# Single_Board.net
KiCad netlist of a schematic drawn in EAGLE
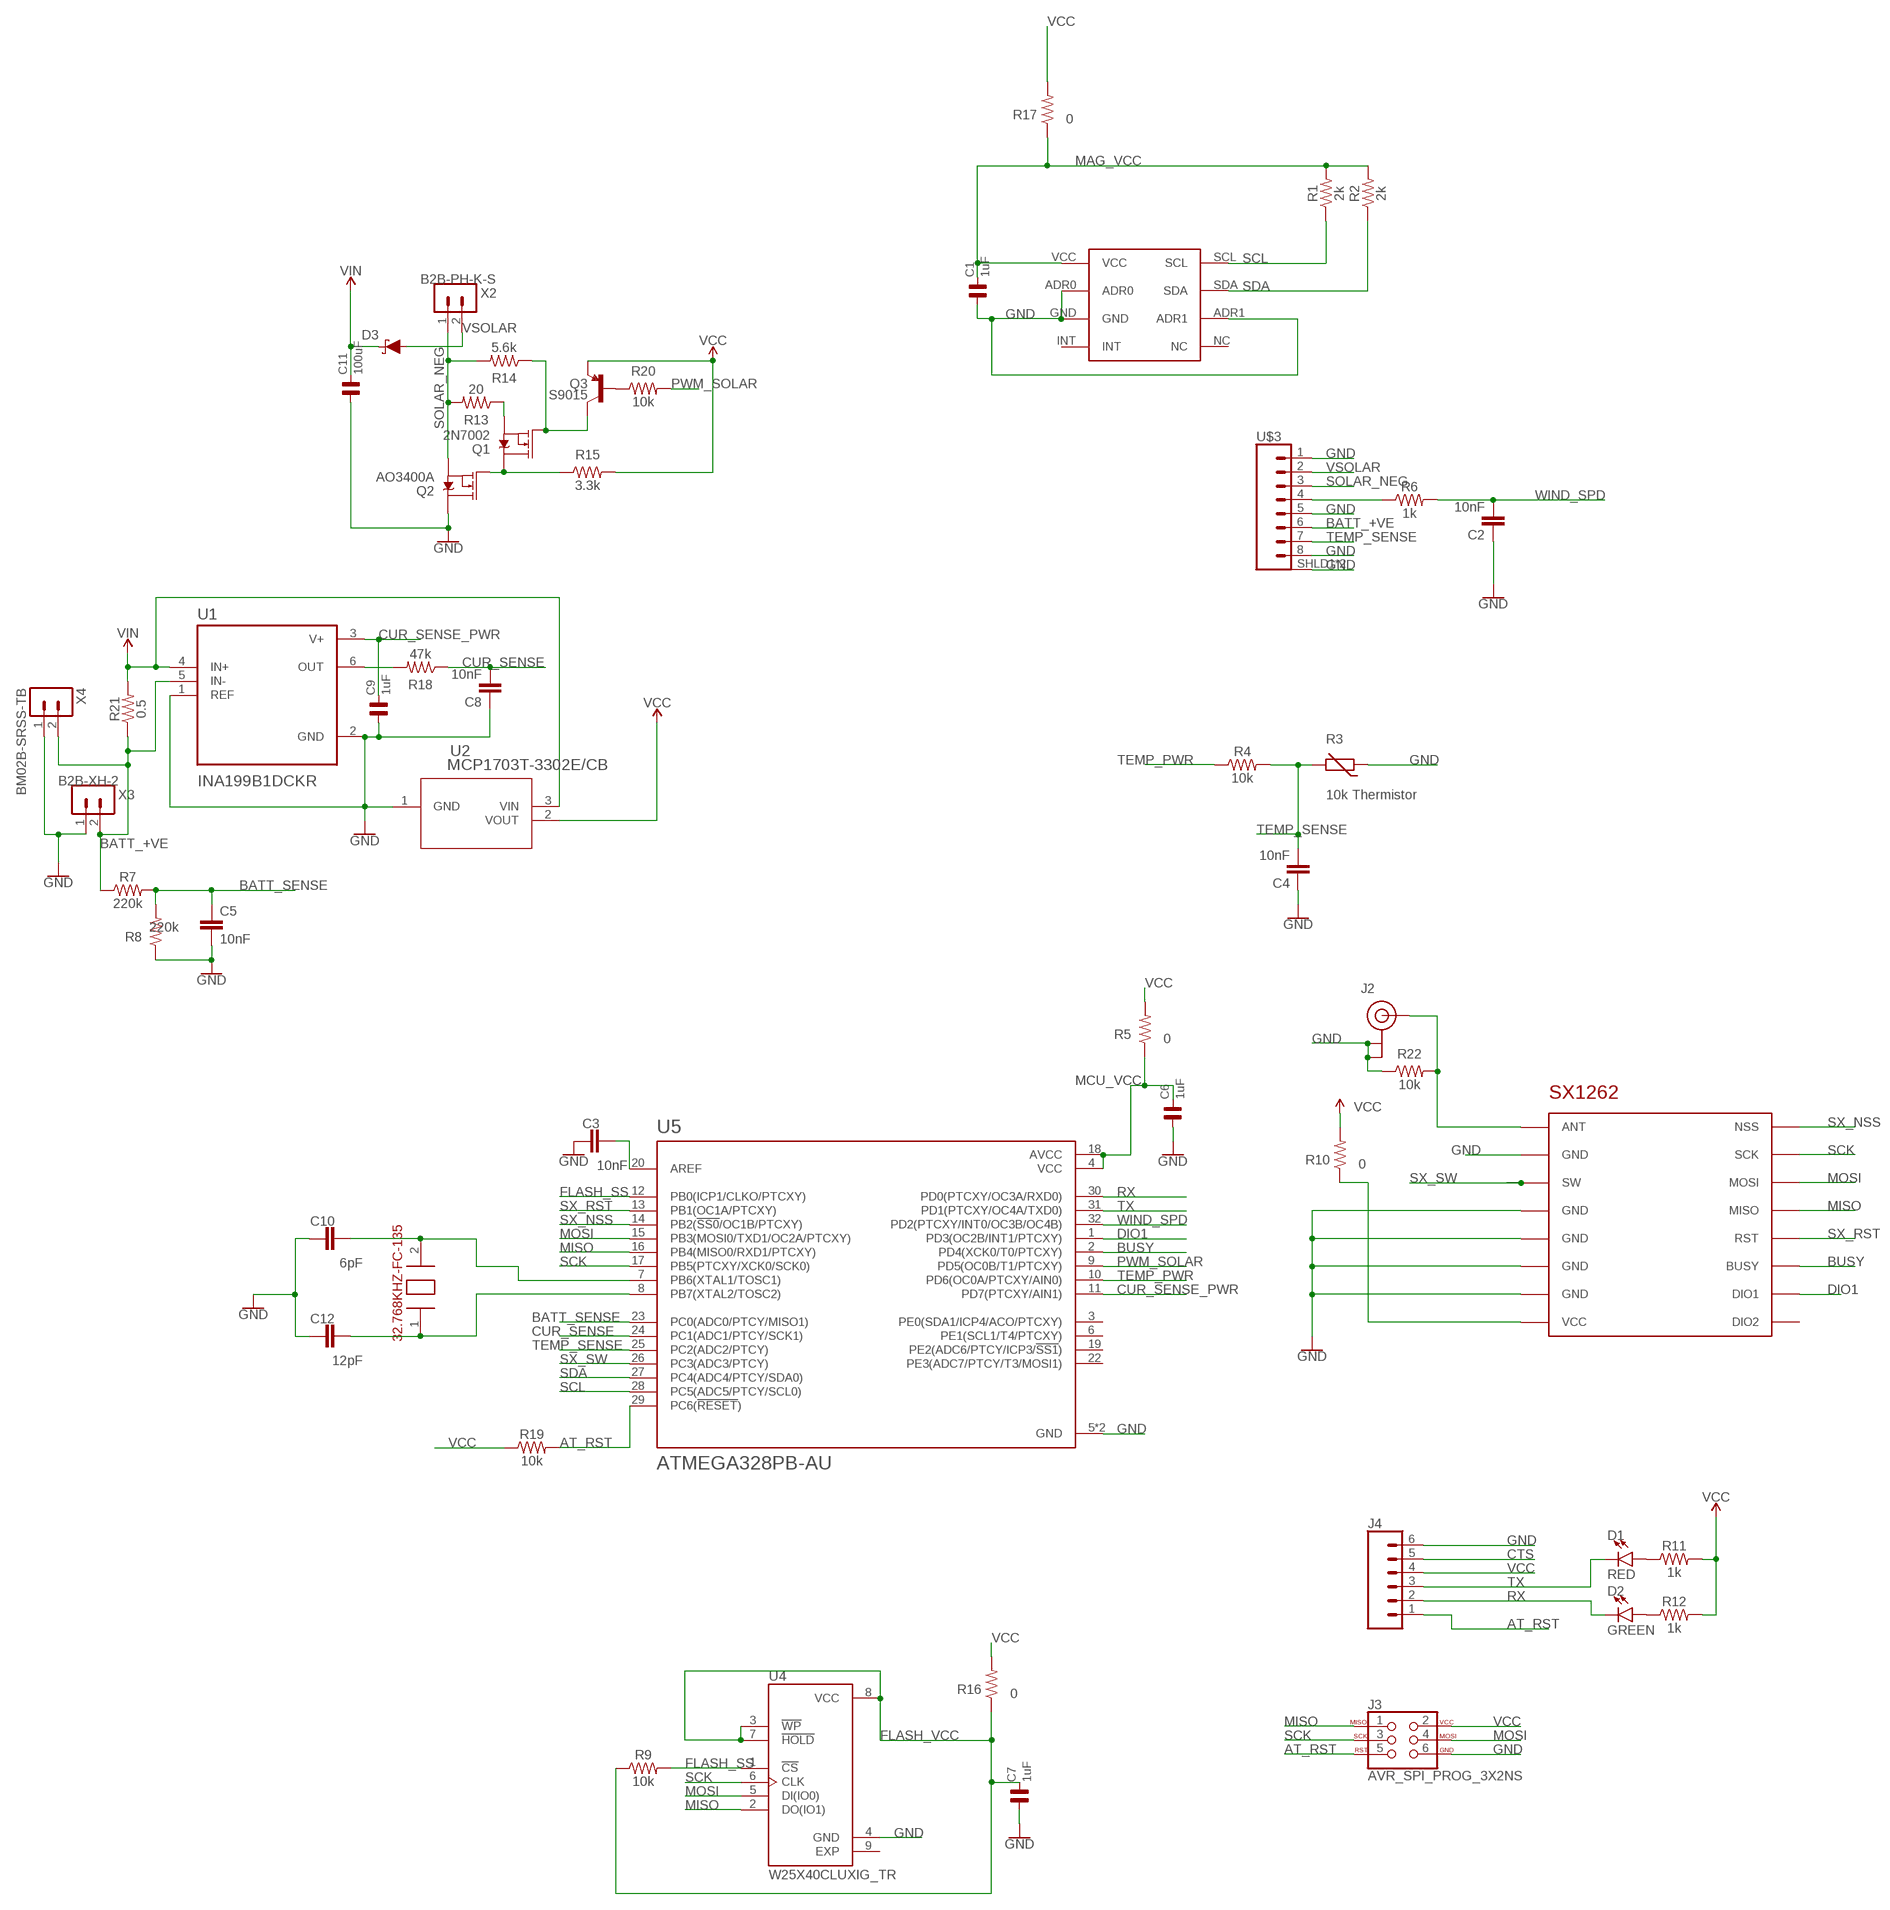
[diagram p0: schematic, sheet 1]

(export (version "E")
  (design (tool "Eeschema 10.0.6"))
  (components
    (comp (ref "C1")
      (value "1uF")
      (footprint "eagle-import:0805")
      (libsource (lib "eagle-import") (part "C0805"))
    )
    (comp (ref "C2")
      (value "10nF")
      (footprint "eagle-import:0603")
      (libsource (lib "eagle-import") (part "10NF-0603-50V-10%"))
    )
    (comp (ref "C3")
      (value "10nF")
      (footprint "eagle-import:0603")
      (libsource (lib "eagle-import") (part "10NF-0603-50V-10%"))
    )
    (comp (ref "C4")
      (value "10nF")
      (footprint "eagle-import:0603")
      (libsource (lib "eagle-import") (part "10NF-0603-50V-10%"))
    )
    (comp (ref "C5")
      (value "10nF")
      (footprint "eagle-import:0603")
      (libsource (lib "eagle-import") (part "10NF-0603-50V-10%"))
    )
    (comp (ref "C6")
      (value "1uF")
      (footprint "eagle-import:0805")
      (libsource (lib "eagle-import") (part "C0805"))
    )
    (comp (ref "C7")
      (value "1uF")
      (footprint "eagle-import:0805")
      (libsource (lib "eagle-import") (part "C0805"))
    )
    (comp (ref "C8")
      (value "10nF")
      (footprint "eagle-import:0603")
      (libsource (lib "eagle-import") (part "10NF-0603-50V-10%"))
    )
    (comp (ref "C9")
      (value "1uF")
      (footprint "eagle-import:0805")
      (libsource (lib "eagle-import") (part "C0805"))
    )
    (comp (ref "C10")
      (value "6pF")
      (footprint "eagle-import:0603")
      (libsource (lib "eagle-import") (part "10NF-0603-50V-10%"))
    )
    (comp (ref "C11")
      (value "100uF")
      (footprint "eagle-import:1206")
      (libsource (lib "eagle-import") (part "C1206"))
    )
    (comp (ref "C12")
      (value "12pF")
      (footprint "eagle-import:0603")
      (libsource (lib "eagle-import") (part "10NF-0603-50V-10%"))
    )
    (comp (ref "D1")
      (value "RED")
      (footprint "eagle-import:LED-1206")
      (libsource (lib "eagle-import") (part "LED-RED1206"))
    )
    (comp (ref "D2")
      (value "GREEN")
      (footprint "eagle-import:LED-1206")
      (libsource (lib "eagle-import") (part "LED-GREEN1206"))
    )
    (comp (ref "D3")
      (value "NSR0240HT1G")
      (footprint "eagle-import:SOD-323")
      (libsource (lib "eagle-import") (part "DIODE-SCHOTTKY-PMEG4005EJ"))
    )
    (comp (ref "J2")
      (value "U.FL")
      (footprint "eagle-import:U.FL")
      (libsource (lib "eagle-import") (part "U.FL"))
    )
    (comp (ref "J3")
      (value "AVR_SPI_PROG_3X2NS")
      (footprint "eagle-import:2X3-NS")
      (libsource (lib "eagle-import") (part "AVR_SPI_PROG_3X2NS"))
    )
    (comp (ref "J4")
      (value "CONN_06NO_SILK_FEMALE_PTH")
      (footprint "eagle-import:1X06_NO_SILK")
      (libsource (lib "eagle-import") (part "CONN_06NO_SILK_FEMALE_PTH"))
    )
    (comp (ref "Q1")
      (value "2N7002")
      (footprint "eagle-import:SOT23-3")
      (libsource (lib "eagle-import") (part "MOSFET-NCH-BSS138"))
    )
    (comp (ref "Q2")
      (value "AO3400A")
      (footprint "eagle-import:SOT23-3")
      (libsource (lib "eagle-import") (part "MOSFET-NCH-BSS138"))
    )
    (comp (ref "Q3")
      (value "S9015")
      (footprint "eagle-import:SOT23-3")
      (libsource (lib "eagle-import") (part "TRANS_PNP-MMBT4403"))
    )
    (comp (ref "R1")
      (value "2k")
      (footprint "eagle-import:0805")
      (libsource (lib "eagle-import") (part "RESISTOR0805"))
    )
    (comp (ref "R2")
      (value "2k")
      (footprint "eagle-import:0805")
      (libsource (lib "eagle-import") (part "RESISTOR0805"))
    )
    (comp (ref "R3")
      (value "10k Thermistor")
      (footprint "eagle-import:R-5")
      (libsource (lib "eagle-import") (part "THERMISTOR-5"))
    )
    (comp (ref "R4")
      (value "10k")
      (footprint "eagle-import:0805")
      (libsource (lib "eagle-import") (part "RESISTOR0805"))
    )
    (comp (ref "R5")
      (value "0")
      (footprint "eagle-import:0805")
      (libsource (lib "eagle-import") (part "RESISTOR0805"))
    )
    (comp (ref "R6")
      (value "1k")
      (footprint "eagle-import:0805")
      (libsource (lib "eagle-import") (part "RESISTOR0805"))
    )
    (comp (ref "R7")
      (value "220k")
      (footprint "eagle-import:0805")
      (libsource (lib "eagle-import") (part "RESISTOR0805"))
    )
    (comp (ref "R8")
      (value "220k")
      (footprint "eagle-import:0805")
      (libsource (lib "eagle-import") (part "RESISTOR0805"))
    )
    (comp (ref "R9")
      (value "10k")
      (footprint "eagle-import:0805")
      (libsource (lib "eagle-import") (part "RESISTOR0805"))
    )
    (comp (ref "R10")
      (value "0")
      (footprint "eagle-import:0805")
      (libsource (lib "eagle-import") (part "RESISTOR0805"))
    )
    (comp (ref "R11")
      (value "1k")
      (footprint "eagle-import:0805")
      (libsource (lib "eagle-import") (part "RESISTOR0805"))
    )
    (comp (ref "R12")
      (value "1k")
      (footprint "eagle-import:0805")
      (libsource (lib "eagle-import") (part "RESISTOR0805"))
    )
    (comp (ref "R13")
      (value "20")
      (footprint "eagle-import:0805")
      (libsource (lib "eagle-import") (part "RESISTOR0805"))
    )
    (comp (ref "R14")
      (value "5.6k")
      (footprint "eagle-import:0805")
      (libsource (lib "eagle-import") (part "RESISTOR0805"))
    )
    (comp (ref "R15")
      (value "3.3k")
      (footprint "eagle-import:0805")
      (libsource (lib "eagle-import") (part "RESISTOR0805"))
    )
    (comp (ref "R16")
      (value "0")
      (footprint "eagle-import:0805")
      (libsource (lib "eagle-import") (part "RESISTOR0805"))
    )
    (comp (ref "R17")
      (value "0")
      (footprint "eagle-import:0805")
      (libsource (lib "eagle-import") (part "RESISTOR0805"))
    )
    (comp (ref "R18")
      (value "47k")
      (footprint "eagle-import:0805")
      (libsource (lib "eagle-import") (part "RESISTOR0805"))
    )
    (comp (ref "R19")
      (value "10k")
      (footprint "eagle-import:0805")
      (libsource (lib "eagle-import") (part "RESISTOR0805"))
    )
    (comp (ref "R20")
      (value "10k")
      (footprint "eagle-import:0805")
      (libsource (lib "eagle-import") (part "RESISTOR0805"))
    )
    (comp (ref "R21")
      (value "0.5")
      (footprint "eagle-import:1206")
      (libsource (lib "eagle-import") (part "RESISTOR1206"))
    )
    (comp (ref "R22")
      (value "10k")
      (footprint "eagle-import:0805")
      (libsource (lib "eagle-import") (part "RESISTOR0805"))
    )
    (comp (ref "U$1")
      (value "ALS31313")
      (footprint "eagle-import:ALS31313-500")
      (libsource (lib "eagle-import") (part "ALS31313"))
    )
    (comp (ref "U$2")
      (value "SX1262")
      (footprint "eagle-import:SX1262")
      (libsource (lib "eagle-import") (part "SX1262"))
    )
    (comp (ref "U$3")
      (value "RJSHE3380")
      (footprint "eagle-import:RJHSE-3380")
      (libsource (lib "eagle-import") (part "RJSHE3380"))
    )
    (comp (ref "U1")
      (value "INA199B1DCKR")
      (footprint "eagle-import:SOT65P210X110-6N")
      (fields
        (field (name "DIGI-KEY_PART_NUMBER") "296-27333-1-ND")
        (field (name "MF") "Texas Instruments")
        (field (name "MP") "INA199A3DCKR")
      )
      (libsource (lib "eagle-import") (part "INA199A3DCKR"))
    )
    (comp (ref "U2")
      (value "MCP1703T-3302E/CB")
      (footprint "eagle-import:SOT-23A_MC")
      (libsource (lib "eagle-import") (part "MCP1703T-3302E/CB"))
    )
    (comp (ref "U4")
      (value "W25X40CLUXIG_TR")
      (footprint "eagle-import:PSON50P300X200X60-9N")
      (fields
        (field (name "DIGI-KEY_PART_NUMBER") "W25X40CLUXIGCT-ND")
        (field (name "MF") "Winbond Electronics")
        (field (name "MP") "W25X40CLUXIG TR")
      )
      (libsource (lib "eagle-import") (part "W25X40CLUXIG_TR"))
    )
    (comp (ref "U5")
      (value "ATMEGA328PB-AU")
      (footprint "eagle-import:QFP80P900X900X120-32N")
      (fields (field (name "MF") "Microchip Technology"))
      (libsource (lib "eagle-import") (part "ATMEGA328PB-AU"))
    )
    (comp (ref "X1")
      (value "32.768KHZ-FC-135")
      (footprint "eagle-import:32.768KHZ-FC-135")
      (libsource (lib "eagle-import") (part "32.768KHZ-FC-135"))
    )
    (comp (ref "X2")
      (value "B2B-PH-K-S")
      (footprint "eagle-import:B2B-PH-K-S")
      (libsource (lib "eagle-import") (part "B2B-PH-K-S"))
    )
    (comp (ref "X3")
      (value "B2B-XH-2")
      (footprint "eagle-import:B2B-XH-A")
      (libsource (lib "eagle-import") (part "B2B-XH-2"))
    )
    (comp (ref "X4")
      (value "BM02B-SRSS-TB")
      (footprint "eagle-import:BM02B-SRSS-TB")
      (libsource (lib "eagle-import") (part "BM02B-SRSS-TB"))
    )
  )
  (nets
    (net (code "1") (name "/AT_RST") (class "Default")
      (node (ref "J3") (pin "5") (pinfunction "5_5") (pintype "passive"))
      (node (ref "J4") (pin "1") (pinfunction "1_1") (pintype "passive"))
      (node (ref "R19") (pin "2") (pinfunction "2_2") (pintype "passive"))
      (node (ref "U5") (pin "29") (pinfunction "PC6(~{RESET})_29") (pintype "bidirectional"))
    )
    (net (code "2") (name "/BATT_+VE") (class "Default")
      (node (ref "R21") (pin "1") (pinfunction "1_1") (pintype "passive"))
      (node (ref "R7") (pin "1") (pinfunction "1_1") (pintype "passive"))
      (node (ref "U$3") (pin "6") (pinfunction "6_6") (pintype "passive"))
      (node (ref "U1") (pin "5") (pinfunction "IN-_5") (pintype "input"))
      (node (ref "X3") (pin "2") (pinfunction "2_2") (pintype "passive"))
      (node (ref "X4") (pin "2") (pinfunction "2_2") (pintype "passive"))
    )
    (net (code "3") (name "/BATT_SENSE") (class "Default")
      (node (ref "C5") (pin "1") (pinfunction "1_1") (pintype "passive"))
      (node (ref "R7") (pin "2") (pinfunction "2_2") (pintype "passive"))
      (node (ref "R8") (pin "2") (pinfunction "2_2") (pintype "passive"))
      (node (ref "U5") (pin "23") (pinfunction "PC0(ADC0/PTCY/MISO1)_23") (pintype "bidirectional"))
    )
    (net (code "4") (name "/BUSY") (class "Default")
      (node (ref "U$2") (pin "BUSY") (pinfunction "BUSY_BUSY") (pintype "bidirectional"))
      (node (ref "U5") (pin "2") (pinfunction "PD4(XCK0/T0/PTCXY)_2") (pintype "bidirectional"))
    )
    (net (code "5") (name "/CTS") (class "Default")
      (node (ref "J4") (pin "5") (pinfunction "5_5") (pintype "passive"))
    )
    (net (code "6") (name "/CUR_SENSE") (class "Default")
      (node (ref "C8") (pin "2") (pinfunction "2_2") (pintype "passive"))
      (node (ref "R18") (pin "1") (pinfunction "1_1") (pintype "passive"))
      (node (ref "U5") (pin "24") (pinfunction "PC1(ADC1/PTCY/SCK1)_24") (pintype "bidirectional"))
    )
    (net (code "7") (name "/CUR_SENSE_PWR") (class "Default")
      (node (ref "C9") (pin "2") (pinfunction "2_2") (pintype "passive"))
      (node (ref "U1") (pin "3") (pinfunction "V+_3") (pintype "power_in"))
      (node (ref "U5") (pin "11") (pinfunction "PD7(PTCXY/AIN1)_11") (pintype "bidirectional"))
    )
    (net (code "8") (name "/DIO1") (class "Default")
      (node (ref "U$2") (pin "DIO1") (pinfunction "DIO1_DIO1") (pintype "bidirectional"))
      (node (ref "U5") (pin "1") (pinfunction "PD3(OC2B/INT1/PTCXY)_1") (pintype "bidirectional"))
    )
    (net (code "9") (name "/EXP") (class "Default")
      (node (ref "U4") (pin "9") (pinfunction "EXP_9") (pintype "power_in"))
    )
    (net (code "10") (name "/FLASH_SS") (class "Default")
      (node (ref "R9") (pin "2") (pinfunction "2_2") (pintype "passive"))
      (node (ref "U4") (pin "1") (pinfunction "~{CS}_1") (pintype "input"))
      (node (ref "U5") (pin "12") (pinfunction "PB0(ICP1/CLKO/PTCXY)_12") (pintype "bidirectional"))
    )
    (net (code "11") (name "/FLASH_VCC") (class "Default")
      (node (ref "C7") (pin "2") (pinfunction "2_2") (pintype "passive"))
      (node (ref "R16") (pin "1") (pinfunction "1_1") (pintype "passive"))
      (node (ref "R9") (pin "1") (pinfunction "1_1") (pintype "passive"))
      (node (ref "U4") (pin "3") (pinfunction "~{WP}_3") (pintype "input"))
      (node (ref "U4") (pin "7") (pinfunction "~{HOLD}_7") (pintype "input"))
      (node (ref "U4") (pin "8") (pinfunction "VCC_8") (pintype "power_in"))
    )
    (net (code "12") (name "/MAG_VCC") (class "Default")
      (node (ref "C1") (pin "2") (pinfunction "2_2") (pintype "passive"))
      (node (ref "R1") (pin "2") (pinfunction "2_2") (pintype "passive"))
      (node (ref "R17") (pin "1") (pinfunction "1_1") (pintype "passive"))
      (node (ref "R2") (pin "2") (pinfunction "2_2") (pintype "passive"))
      (node (ref "U$1") (pin "VCC") (pinfunction "VCC_VCC") (pintype "power_in"))
    )
    (net (code "13") (name "/MCU_VCC") (class "Default")
      (node (ref "C6") (pin "2") (pinfunction "2_2") (pintype "passive"))
      (node (ref "R5") (pin "1") (pinfunction "1_1") (pintype "passive"))
      (node (ref "U5") (pin "18") (pinfunction "AVCC_18") (pintype "power_in"))
      (node (ref "U5") (pin "4") (pinfunction "VCC_4") (pintype "power_in"))
    )
    (net (code "14") (name "/MISO") (class "Default")
      (node (ref "J3") (pin "1") (pinfunction "1_1") (pintype "passive"))
      (node (ref "U$2") (pin "MISO") (pinfunction "MISO_MISO") (pintype "bidirectional"))
      (node (ref "U4") (pin "2") (pinfunction "DO(IO1)_2") (pintype "bidirectional"))
      (node (ref "U5") (pin "16") (pinfunction "PB4(MISO0/RXD1/PTCXY)_16") (pintype "bidirectional"))
    )
    (net (code "15") (name "/MOSI") (class "Default")
      (node (ref "J3") (pin "4") (pinfunction "4_4") (pintype "passive"))
      (node (ref "U$2") (pin "MOSI") (pinfunction "MOSI_MOSI") (pintype "bidirectional"))
      (node (ref "U4") (pin "5") (pinfunction "DI(IO0)_5") (pintype "bidirectional"))
      (node (ref "U5") (pin "15") (pinfunction "PB3(MOSI0/TXD1/OC2A/PTCXY)_15") (pintype "bidirectional"))
    )
    (net (code "16") (name "/PWM_SOLAR") (class "Default")
      (node (ref "R20") (pin "2") (pinfunction "2_2") (pintype "passive"))
      (node (ref "U5") (pin "9") (pinfunction "PD5(OC0B/T1/PTCXY)_9") (pintype "bidirectional"))
    )
    (net (code "17") (name "/RX") (class "Default")
      (node (ref "D2") (pin "C") (pinfunction "C_C") (pintype "passive"))
      (node (ref "J4") (pin "2") (pinfunction "2_2") (pintype "passive"))
      (node (ref "U5") (pin "30") (pinfunction "PD0(PTCXY/OC3A/RXD0)_30") (pintype "bidirectional"))
    )
    (net (code "18") (name "/SCK") (class "Default")
      (node (ref "J3") (pin "3") (pinfunction "3_3") (pintype "passive"))
      (node (ref "U$2") (pin "SCK") (pinfunction "SCK_SCK") (pintype "bidirectional"))
      (node (ref "U4") (pin "6") (pinfunction "CLK_6") (pintype "input"))
      (node (ref "U5") (pin "17") (pinfunction "PB5(PTCXY/XCK0/SCK0)_17") (pintype "bidirectional"))
    )
    (net (code "19") (name "/SCL") (class "Default")
      (node (ref "R1") (pin "1") (pinfunction "1_1") (pintype "passive"))
      (node (ref "U$1") (pin "SCL") (pinfunction "SCL_SCL") (pintype "input"))
      (node (ref "U5") (pin "28") (pinfunction "PC5(ADC5/PTCY/SCL0)_28") (pintype "bidirectional"))
    )
    (net (code "20") (name "/SDA") (class "Default")
      (node (ref "R2") (pin "1") (pinfunction "1_1") (pintype "passive"))
      (node (ref "U$1") (pin "SDA") (pinfunction "SDA_SDA") (pintype "bidirectional"))
      (node (ref "U5") (pin "27") (pinfunction "PC4(ADC4/PTCY/SDA0)_27") (pintype "bidirectional"))
    )
    (net (code "21") (name "/SOLAR_NEG") (class "Default")
      (node (ref "Q2") (pin "2") (pinfunction "S_2") (pintype "bidirectional"))
      (node (ref "R13") (pin "2") (pinfunction "2_2") (pintype "passive"))
      (node (ref "R14") (pin "2") (pinfunction "2_2") (pintype "passive"))
      (node (ref "U$3") (pin "3") (pinfunction "3_3") (pintype "passive"))
      (node (ref "X2") (pin "1") (pinfunction "1_1") (pintype "passive"))
    )
    (net (code "22") (name "/SX_NSS") (class "Default")
      (node (ref "U$2") (pin "NSS") (pinfunction "NSS_NSS") (pintype "bidirectional"))
      (node (ref "U5") (pin "14") (pinfunction "PB2(~{SS0}/OC1B/PTCXY)_14") (pintype "bidirectional"))
    )
    (net (code "23") (name "/SX_RST") (class "Default")
      (node (ref "U$2") (pin "RST") (pinfunction "RST_RST") (pintype "bidirectional"))
      (node (ref "U5") (pin "13") (pinfunction "PB1(OC1A/PTCXY)_13") (pintype "bidirectional"))
    )
    (net (code "24") (name "/SX_SW") (class "Default")
      (node (ref "U$2") (pin "SW") (pinfunction "SW_SW") (pintype "bidirectional"))
      (node (ref "U5") (pin "26") (pinfunction "PC3(ADC3/PTCY)_26") (pintype "bidirectional"))
    )
    (net (code "25") (name "/TEMP_PWR") (class "Default")
      (node (ref "R4") (pin "1") (pinfunction "1_1") (pintype "passive"))
      (node (ref "U5") (pin "10") (pinfunction "PD6(OC0A/PTCXY/AIN0)_10") (pintype "bidirectional"))
    )
    (net (code "26") (name "/TEMP_SENSE") (class "Default")
      (node (ref "C4") (pin "2") (pinfunction "2_2") (pintype "passive"))
      (node (ref "R3") (pin "2") (pinfunction "2_2") (pintype "passive"))
      (node (ref "R4") (pin "2") (pinfunction "2_2") (pintype "passive"))
      (node (ref "U$3") (pin "7") (pinfunction "7_7") (pintype "passive"))
      (node (ref "U5") (pin "25") (pinfunction "PC2(ADC2/PTCY)_25") (pintype "bidirectional"))
    )
    (net (code "27") (name "/TX") (class "Default")
      (node (ref "D1") (pin "C") (pinfunction "C_C") (pintype "passive"))
      (node (ref "J4") (pin "3") (pinfunction "3_3") (pintype "passive"))
      (node (ref "U5") (pin "31") (pinfunction "PD1(PTCXY/OC4A/TXD0)_31") (pintype "bidirectional"))
    )
    (net (code "28") (name "/VSOLAR") (class "Default")
      (node (ref "D3") (pin "A") (pinfunction "A_A") (pintype "passive"))
      (node (ref "U$3") (pin "2") (pinfunction "2_2") (pintype "passive"))
      (node (ref "X2") (pin "2") (pinfunction "2_2") (pintype "passive"))
    )
    (net (code "29") (name "/WIND_SPD") (class "Default")
      (node (ref "C2") (pin "2") (pinfunction "2_2") (pintype "passive"))
      (node (ref "R6") (pin "2") (pinfunction "2_2") (pintype "passive"))
      (node (ref "U5") (pin "32") (pinfunction "PD2(PTCXY/INT0/OC3B/OC4B)_32") (pintype "bidirectional"))
    )
    (net (code "30") (name "GND") (class "Default")
      (node (ref "C1") (pin "1") (pinfunction "1_1") (pintype "passive"))
      (node (ref "C10") (pin "1") (pinfunction "1_1") (pintype "passive"))
      (node (ref "C11") (pin "1") (pinfunction "1_1") (pintype "passive"))
      (node (ref "C12") (pin "1") (pinfunction "1_1") (pintype "passive"))
      (node (ref "C2") (pin "1") (pinfunction "1_1") (pintype "passive"))
      (node (ref "C3") (pin "1") (pinfunction "1_1") (pintype "passive"))
      (node (ref "C4") (pin "1") (pinfunction "1_1") (pintype "passive"))
      (node (ref "C5") (pin "2") (pinfunction "2_2") (pintype "passive"))
      (node (ref "C6") (pin "1") (pinfunction "1_1") (pintype "passive"))
      (node (ref "C7") (pin "1") (pinfunction "1_1") (pintype "passive"))
      (node (ref "C8") (pin "1") (pinfunction "1_1") (pintype "passive"))
      (node (ref "C9") (pin "1") (pinfunction "1_1") (pintype "passive"))
      (node (ref "J2") (pin "1") (pinfunction "GND_1") (pintype "bidirectional"))
      (node (ref "J2") (pin "2") (pinfunction "GND_2") (pintype "bidirectional"))
      (node (ref "J3") (pin "6") (pinfunction "6_6") (pintype "passive"))
      (node (ref "J4") (pin "6") (pinfunction "6_6") (pintype "passive"))
      (node (ref "Q2") (pin "3") (pinfunction "D_3") (pintype "bidirectional"))
      (node (ref "R22") (pin "1") (pinfunction "1_1") (pintype "passive"))
      (node (ref "R3") (pin "1") (pinfunction "1_1") (pintype "passive"))
      (node (ref "R8") (pin "1") (pinfunction "1_1") (pintype "passive"))
      (node (ref "U$1") (pin "ADR0") (pinfunction "ADR0_ADR0") (pintype "input"))
      (node (ref "U$1") (pin "ADR1") (pinfunction "ADR1_ADR1") (pintype "input"))
      (node (ref "U$1") (pin "GND") (pinfunction "GND_GND") (pintype "power_in"))
      (node (ref "U$2") (pin "GND@1") (pinfunction "GND_GND@1") (pintype "bidirectional"))
      (node (ref "U$2") (pin "GND@2") (pinfunction "GND_GND@2") (pintype "bidirectional"))
      (node (ref "U$2") (pin "GND@3") (pinfunction "GND_GND@3") (pintype "bidirectional"))
      (node (ref "U$2") (pin "GND@4") (pinfunction "GND_GND@4") (pintype "bidirectional"))
      (node (ref "U$2") (pin "GND@5") (pinfunction "GND_GND@5") (pintype "bidirectional"))
      (node (ref "U$3") (pin "1") (pinfunction "1_1") (pintype "passive"))
      (node (ref "U$3") (pin "5") (pinfunction "5_5") (pintype "passive"))
      (node (ref "U$3") (pin "8") (pinfunction "8_8") (pintype "passive"))
      (node (ref "U$3") (pin "SHLD1") (pinfunction "SHLD_SHLD1") (pintype "passive"))
      (node (ref "U$3") (pin "SHLD2") (pinfunction "SHLD_SHLD2") (pintype "passive"))
      (node (ref "U1") (pin "1") (pinfunction "REF_1") (pintype "input"))
      (node (ref "U1") (pin "2") (pinfunction "GND_2") (pintype "power_in"))
      (node (ref "U2") (pin "1") (pinfunction "GND_1") (pintype "passive"))
      (node (ref "U4") (pin "4") (pinfunction "GND_4") (pintype "power_in"))
      (node (ref "U5") (pin "21") (pinfunction "GND_21") (pintype "power_in"))
      (node (ref "U5") (pin "5") (pinfunction "GND_5") (pintype "power_in"))
      (node (ref "X3") (pin "1") (pinfunction "1_1") (pintype "passive"))
      (node (ref "X4") (pin "1") (pinfunction "1_1") (pintype "passive"))
    )
    (net (code "31") (name "Net-(D1-PadA)") (class "Default")
      (node (ref "D1") (pin "A") (pinfunction "A_A") (pintype "passive"))
      (node (ref "R11") (pin "1") (pinfunction "1_1") (pintype "passive"))
    )
    (net (code "32") (name "Net-(D2-PadA)") (class "Default")
      (node (ref "D2") (pin "A") (pinfunction "A_A") (pintype "passive"))
      (node (ref "R12") (pin "1") (pinfunction "1_1") (pintype "passive"))
    )
    (net (code "33") (name "Net-(J2-SIGNAL)") (class "Default")
      (node (ref "J2") (pin "FEED") (pinfunction "SIGNAL_FEED") (pintype "bidirectional"))
      (node (ref "R22") (pin "2") (pinfunction "2_2") (pintype "passive"))
      (node (ref "U$2") (pin "ANT") (pinfunction "ANT_ANT") (pintype "bidirectional"))
    )
    (net (code "34") (name "Net-(Q1-D)") (class "Default")
      (node (ref "Q1") (pin "3") (pinfunction "D_3") (pintype "bidirectional"))
      (node (ref "Q2") (pin "1") (pinfunction "G_1") (pintype "bidirectional"))
      (node (ref "R15") (pin "1") (pinfunction "1_1") (pintype "passive"))
    )
    (net (code "35") (name "Net-(Q1-G)") (class "Default")
      (node (ref "Q1") (pin "1") (pinfunction "G_1") (pintype "bidirectional"))
      (node (ref "Q3") (pin "3") (pinfunction "C_3") (pintype "passive"))
      (node (ref "R14") (pin "1") (pinfunction "1_1") (pintype "passive"))
    )
    (net (code "36") (name "Net-(Q1-S)") (class "Default")
      (node (ref "Q1") (pin "2") (pinfunction "S_2") (pintype "bidirectional"))
      (node (ref "R13") (pin "1") (pinfunction "1_1") (pintype "passive"))
    )
    (net (code "37") (name "Net-(Q3-B)") (class "Default")
      (node (ref "Q3") (pin "1") (pinfunction "B_1") (pintype "passive"))
      (node (ref "R20") (pin "1") (pinfunction "1_1") (pintype "passive"))
    )
    (net (code "38") (name "Net-(R6-Pad1)") (class "Default")
      (node (ref "R6") (pin "1") (pinfunction "1_1") (pintype "passive"))
      (node (ref "U$3") (pin "4") (pinfunction "4_4") (pintype "passive"))
    )
    (net (code "39") (name "Net-(R10-Pad1)") (class "Default")
      (node (ref "R10") (pin "1") (pinfunction "1_1") (pintype "passive"))
      (node (ref "U$2") (pin "VCC") (pinfunction "VCC_VCC") (pintype "bidirectional"))
    )
    (net (code "40") (name "Net-(U1-OUT)") (class "Default")
      (node (ref "R18") (pin "2") (pinfunction "2_2") (pintype "passive"))
      (node (ref "U1") (pin "6") (pinfunction "OUT_6") (pintype "output"))
    )
    (net (code "41") (name "Net-(U5-AREF)") (class "Default")
      (node (ref "C3") (pin "2") (pinfunction "2_2") (pintype "passive"))
      (node (ref "U5") (pin "20") (pinfunction "AREF_20") (pintype "input"))
    )
    (net (code "42") (name "Net-(U5-PB6(XTAL1{slash}TOSC1))") (class "Default")
      (node (ref "C10") (pin "2") (pinfunction "2_2") (pintype "passive"))
      (node (ref "U5") (pin "7") (pinfunction "PB6(XTAL1/TOSC1)_7") (pintype "bidirectional"))
      (node (ref "X1") (pin "2") (pinfunction "2.XIN_2") (pintype "bidirectional"))
    )
    (net (code "43") (name "Net-(U5-PB7(XTAL2{slash}TOSC2))") (class "Default")
      (node (ref "C12") (pin "2") (pinfunction "2_2") (pintype "passive"))
      (node (ref "U5") (pin "8") (pinfunction "PB7(XTAL2/TOSC2)_8") (pintype "bidirectional"))
      (node (ref "X1") (pin "1") (pinfunction "1.XIN_1") (pintype "bidirectional"))
    )
    (net (code "44") (name "VCC") (class "Default")
      (node (ref "J3") (pin "2") (pinfunction "2_2") (pintype "passive"))
      (node (ref "J4") (pin "4") (pinfunction "4_4") (pintype "passive"))
      (node (ref "Q3") (pin "2") (pinfunction "E_2") (pintype "passive"))
      (node (ref "R10") (pin "2") (pinfunction "2_2") (pintype "passive"))
      (node (ref "R11") (pin "2") (pinfunction "2_2") (pintype "passive"))
      (node (ref "R12") (pin "2") (pinfunction "2_2") (pintype "passive"))
      (node (ref "R15") (pin "2") (pinfunction "2_2") (pintype "passive"))
      (node (ref "R16") (pin "2") (pinfunction "2_2") (pintype "passive"))
      (node (ref "R17") (pin "2") (pinfunction "2_2") (pintype "passive"))
      (node (ref "R19") (pin "1") (pinfunction "1_1") (pintype "passive"))
      (node (ref "R5") (pin "2") (pinfunction "2_2") (pintype "passive"))
      (node (ref "U2") (pin "2") (pinfunction "VOUT_2") (pintype "passive"))
    )
    (net (code "45") (name "VIN") (class "Default")
      (node (ref "C11") (pin "2") (pinfunction "2_2") (pintype "passive"))
      (node (ref "D3") (pin "C") (pinfunction "C_C") (pintype "passive"))
      (node (ref "R21") (pin "2") (pinfunction "2_2") (pintype "passive"))
      (node (ref "U1") (pin "4") (pinfunction "IN+_4") (pintype "input"))
      (node (ref "U2") (pin "3") (pinfunction "VIN_3") (pintype "passive"))
    )
    (net (code "46") (name "unconnected-(U$1-PadINT)") (class "Default")
      (node (ref "U$1") (pin "INT") (pinfunction "INT_INT") (pintype "output"))
    )
    (net (code "47") (name "unconnected-(U$1-PadNC)") (class "Default")
      (node (ref "U$1") (pin "NC") (pinfunction "NC_NC") (pintype "no_connect"))
    )
    (net (code "48") (name "unconnected-(U$2-PadDIO2)") (class "Default")
      (node (ref "U$2") (pin "DIO2") (pinfunction "DIO2_DIO2") (pintype "bidirectional"))
    )
    (net (code "49") (name "unconnected-(U5-PE0(SDA1{slash}ICP4{slash}ACO{slash}PTCXY)-Pad3)") (class "Default")
      (node (ref "U5") (pin "3") (pinfunction "PE0(SDA1/ICP4/ACO/PTCXY)_3") (pintype "bidirectional"))
    )
    (net (code "50") (name "unconnected-(U5-PE1(SCL1{slash}T4{slash}PTCXY)-Pad6)") (class "Default")
      (node (ref "U5") (pin "6") (pinfunction "PE1(SCL1/T4/PTCXY)_6") (pintype "bidirectional"))
    )
    (net (code "51") (name "unconnected-(U5-PE2(ADC6{slash}PTCY{slash}ICP3{slash}~{SS1})-Pad19)") (class "Default")
      (node (ref "U5") (pin "19") (pinfunction "PE2(ADC6/PTCY/ICP3/~{SS1})_19") (pintype "bidirectional"))
    )
    (net (code "52") (name "unconnected-(U5-PE3(ADC7{slash}PTCY{slash}T3{slash}MOSI1)-Pad22)") (class "Default")
      (node (ref "U5") (pin "22") (pinfunction "PE3(ADC7/PTCY/T3/MOSI1)_22") (pintype "bidirectional"))
    )
  )
)
